# elric20-01A.net
KiCad netlist of a schematic drawn in EAGLE
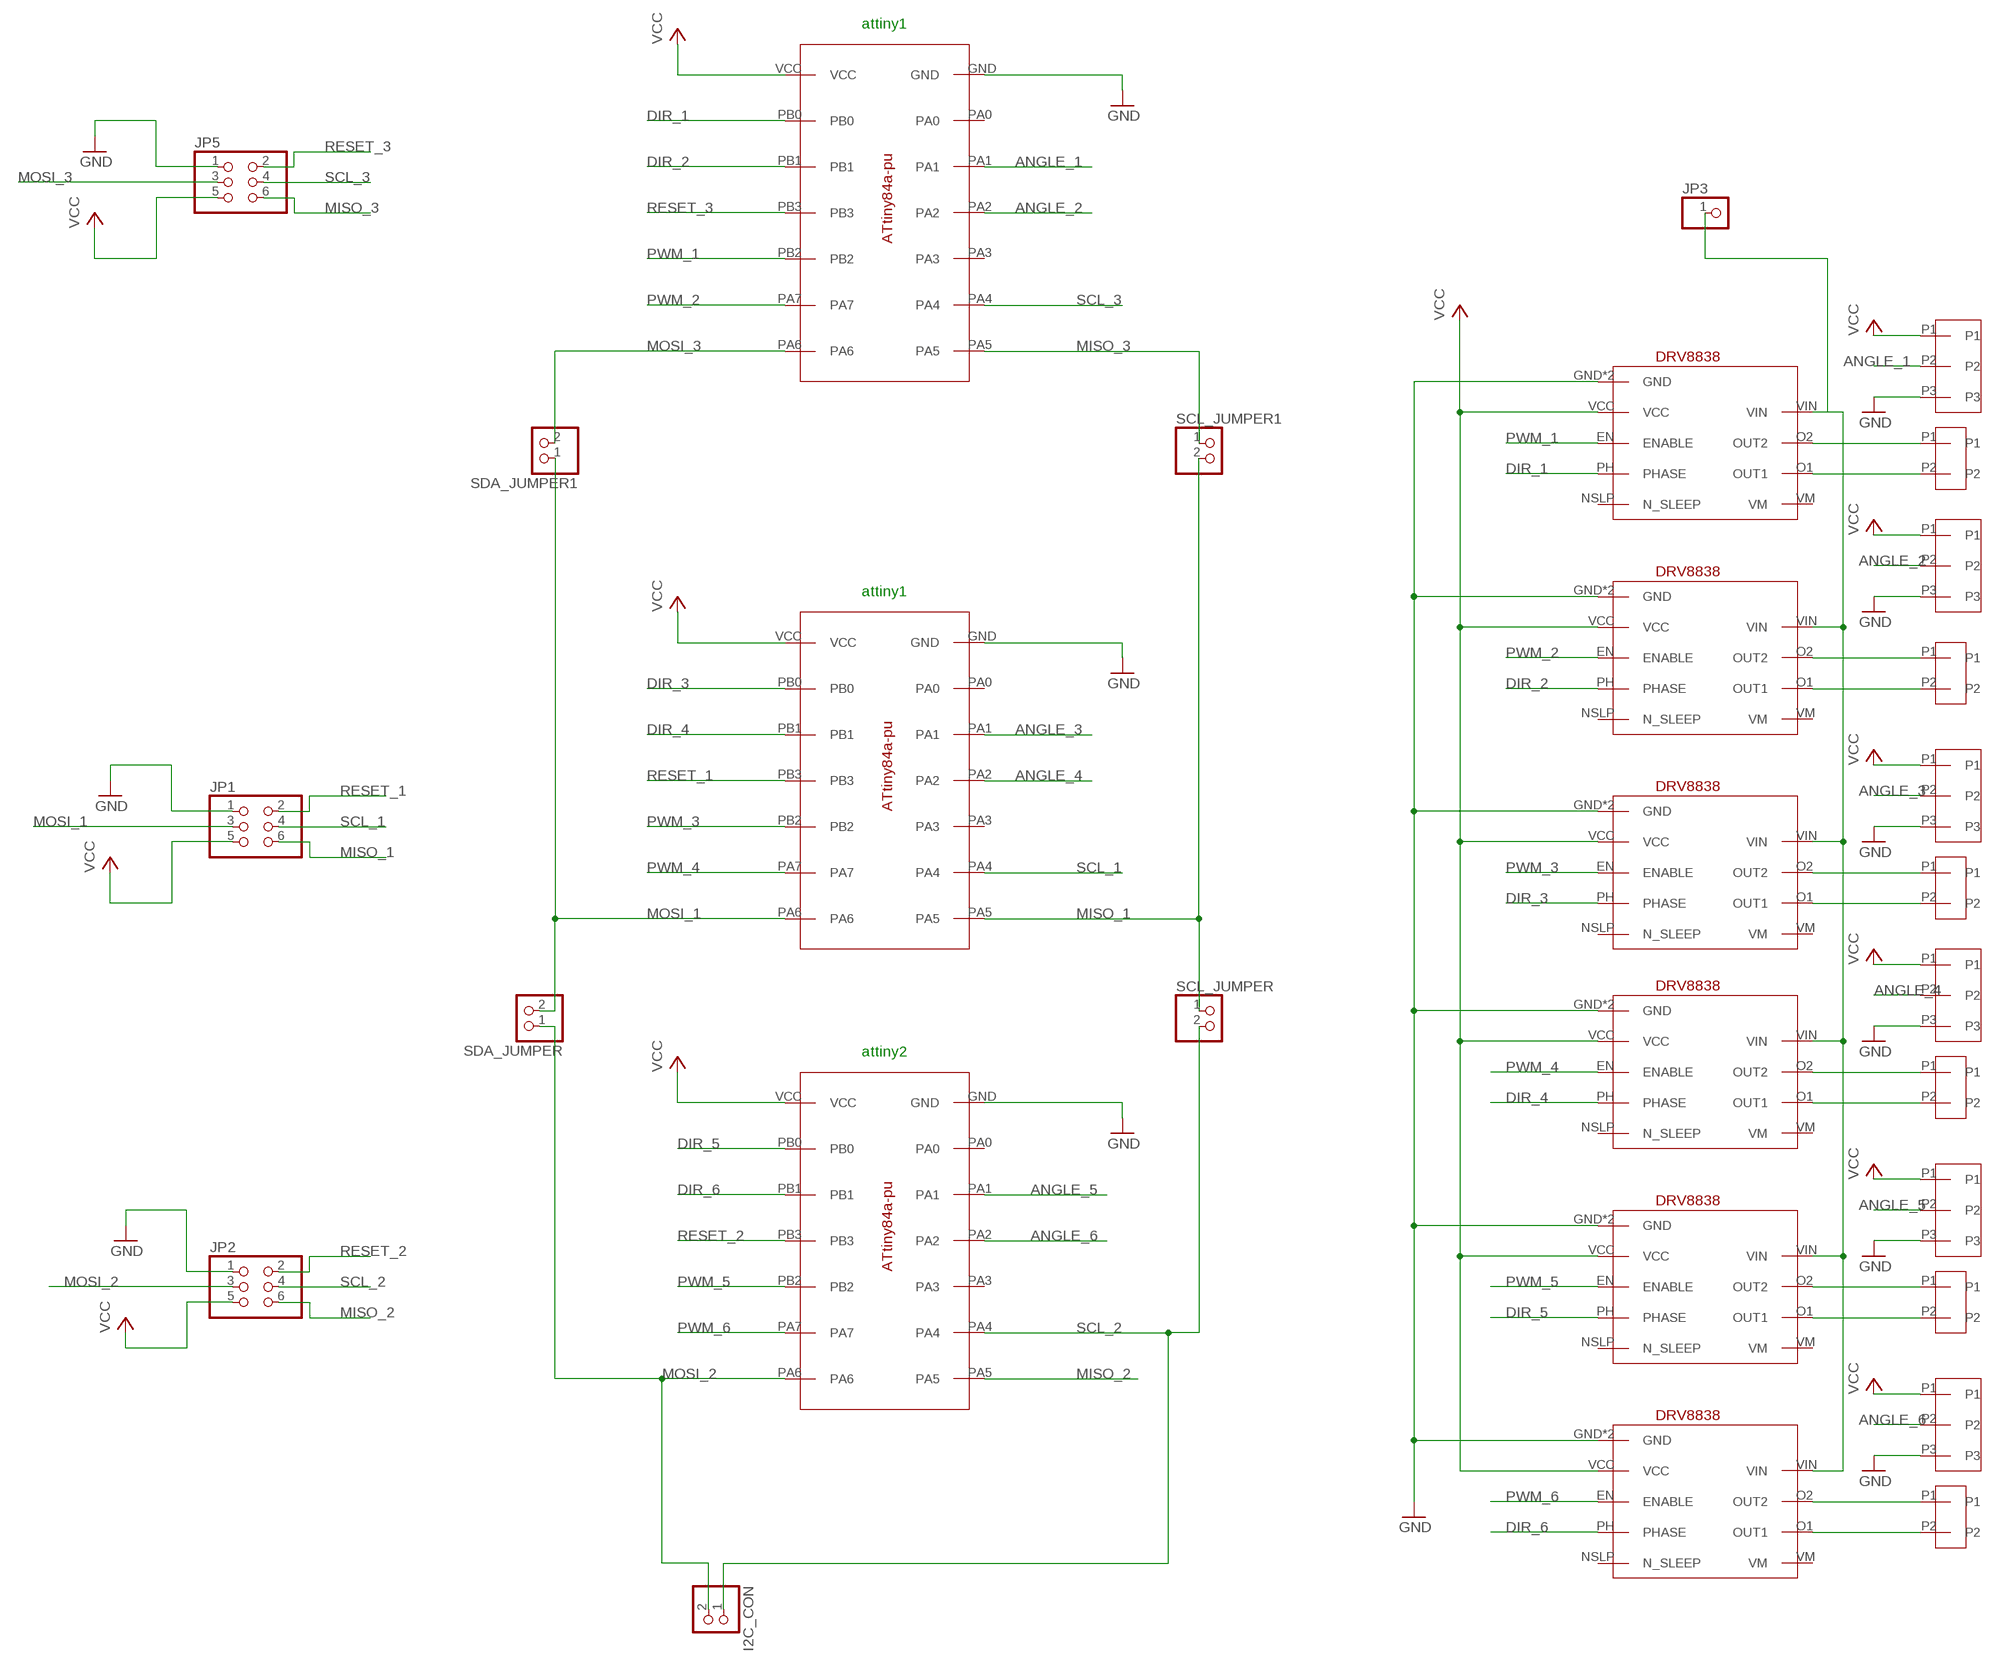
[diagram p0: schematic, sheet 1]

(export (version "E")
  (design (tool "Eeschema 10.0.6"))
  (components
    (comp (ref "I2C_CON")
      (value "PINHD-1X2")
      (footprint "eagle-import:1X02")
      (libsource (lib "eagle-import") (part "PINHD-1X2"))
    )
    (comp (ref "JP1")
      (value "PINHD-2X3")
      (footprint "eagle-import:2X03")
      (libsource (lib "eagle-import") (part "PINHD-2X3"))
    )
    (comp (ref "JP2")
      (value "PINHD-2X3")
      (footprint "eagle-import:2X03")
      (libsource (lib "eagle-import") (part "PINHD-2X3"))
    )
    (comp (ref "JP3")
      (value "PINHD-1X1")
      (footprint "eagle-import:1X01")
      (libsource (lib "eagle-import") (part "PINHD-1X1"))
    )
    (comp (ref "JP5")
      (value "PINHD-2X3")
      (footprint "eagle-import:2X03")
      (libsource (lib "eagle-import") (part "PINHD-2X3"))
    )
    (comp (ref "SCL_JUMPER")
      (value "PINHD-1X2")
      (footprint "eagle-import:1X02")
      (libsource (lib "eagle-import") (part "PINHD-1X2"))
    )
    (comp (ref "SCL_JUMPER1")
      (value "PINHD-1X2")
      (footprint "eagle-import:1X02")
      (libsource (lib "eagle-import") (part "PINHD-1X2"))
    )
    (comp (ref "SDA_JUMPER")
      (value "PINHD-1X2")
      (footprint "eagle-import:1X02")
      (libsource (lib "eagle-import") (part "PINHD-1X2"))
    )
    (comp (ref "SDA_JUMPER1")
      (value "PINHD-1X2")
      (footprint "eagle-import:1X02")
      (libsource (lib "eagle-import") (part "PINHD-1X2"))
    )
    (comp (ref "U$1")
      (value "ATTINY84A-PU")
      (footprint "eagle-import:ATTINY84A-PU")
      (libsource (lib "eagle-import") (part "ATTINY84A-PU"))
    )
    (comp (ref "U$2")
      (value "DRV8838")
      (footprint "eagle-import:DRV8838")
      (libsource (lib "eagle-import") (part "DRV8838"))
    )
    (comp (ref "U$3")
      (value "DRV8838")
      (footprint "eagle-import:DRV8838")
      (libsource (lib "eagle-import") (part "DRV8838"))
    )
    (comp (ref "U$4")
      (value "DRV8838")
      (footprint "eagle-import:DRV8838")
      (libsource (lib "eagle-import") (part "DRV8838"))
    )
    (comp (ref "U$5")
      (value "DRV8838")
      (footprint "eagle-import:DRV8838")
      (libsource (lib "eagle-import") (part "DRV8838"))
    )
    (comp (ref "U$6")
      (value "DRV8838")
      (footprint "eagle-import:DRV8838")
      (libsource (lib "eagle-import") (part "DRV8838"))
    )
    (comp (ref "U$7")
      (value "DRV8838")
      (footprint "eagle-import:DRV8838")
      (libsource (lib "eagle-import") (part "DRV8838"))
    )
    (comp (ref "U$8")
      (value "ATTINY84A-PU")
      (footprint "eagle-import:ATTINY84A-PU")
      (libsource (lib "eagle-import") (part "ATTINY84A-PU"))
    )
    (comp (ref "U$9")
      (value "PAD_SMD_X2_BIG")
      (footprint "eagle-import:PAD_SMD_X2_BIG")
      (libsource (lib "eagle-import") (part "PAD_SMD_X2_BIG"))
    )
    (comp (ref "U$10")
      (value "PAD_SMD_X2_BIG")
      (footprint "eagle-import:PAD_SMD_X2_BIG")
      (libsource (lib "eagle-import") (part "PAD_SMD_X2_BIG"))
    )
    (comp (ref "U$11")
      (value "PAD_SMD_X2_BIG")
      (footprint "eagle-import:PAD_SMD_X2_BIG")
      (libsource (lib "eagle-import") (part "PAD_SMD_X2_BIG"))
    )
    (comp (ref "U$12")
      (value "PAD_SMD_X2_BIG")
      (footprint "eagle-import:PAD_SMD_X2_BIG")
      (libsource (lib "eagle-import") (part "PAD_SMD_X2_BIG"))
    )
    (comp (ref "U$13")
      (value "PAD_SMD_X2_BIG")
      (footprint "eagle-import:PAD_SMD_X2_BIG")
      (libsource (lib "eagle-import") (part "PAD_SMD_X2_BIG"))
    )
    (comp (ref "U$14")
      (value "PAD_SMD_X2_BIG")
      (footprint "eagle-import:PAD_SMD_X2_BIG")
      (libsource (lib "eagle-import") (part "PAD_SMD_X2_BIG"))
    )
    (comp (ref "U$15")
      (value "PAD_SMD_X3")
      (footprint "eagle-import:PAD_SMD_X3")
      (libsource (lib "eagle-import") (part "PAD_SMD_X3"))
    )
    (comp (ref "U$16")
      (value "PAD_SMD_X3")
      (footprint "eagle-import:PAD_SMD_X3")
      (libsource (lib "eagle-import") (part "PAD_SMD_X3"))
    )
    (comp (ref "U$17")
      (value "PAD_SMD_X3")
      (footprint "eagle-import:PAD_SMD_X3")
      (libsource (lib "eagle-import") (part "PAD_SMD_X3"))
    )
    (comp (ref "U$18")
      (value "PAD_SMD_X3")
      (footprint "eagle-import:PAD_SMD_X3")
      (libsource (lib "eagle-import") (part "PAD_SMD_X3"))
    )
    (comp (ref "U$19")
      (value "PAD_SMD_X3")
      (footprint "eagle-import:PAD_SMD_X3")
      (libsource (lib "eagle-import") (part "PAD_SMD_X3"))
    )
    (comp (ref "U$20")
      (value "PAD_SMD_X3")
      (footprint "eagle-import:PAD_SMD_X3")
      (libsource (lib "eagle-import") (part "PAD_SMD_X3"))
    )
    (comp (ref "U$21")
      (value "ATTINY84A-PU")
      (footprint "eagle-import:ATTINY84A-PU")
      (libsource (lib "eagle-import") (part "ATTINY84A-PU"))
    )
  )
  (nets
    (net (code "1") (name "/ANGLE_1") (class "Default")
      (node (ref "U$20") (pin "P2") (pinfunction "P2_P2") (pintype "bidirectional"))
      (node (ref "U$21") (pin "PA1") (pinfunction "PA1_PA1") (pintype "bidirectional"))
    )
    (net (code "2") (name "/ANGLE_2") (class "Default")
      (node (ref "U$19") (pin "P2") (pinfunction "P2_P2") (pintype "bidirectional"))
      (node (ref "U$21") (pin "PA2") (pinfunction "PA2_PA2") (pintype "bidirectional"))
    )
    (net (code "3") (name "/ANGLE_3") (class "Default")
      (node (ref "U$18") (pin "P2") (pinfunction "P2_P2") (pintype "bidirectional"))
      (node (ref "U$8") (pin "PA1") (pinfunction "PA1_PA1") (pintype "bidirectional"))
    )
    (net (code "4") (name "/ANGLE_4") (class "Default")
      (node (ref "U$17") (pin "P2") (pinfunction "P2_P2") (pintype "bidirectional"))
      (node (ref "U$8") (pin "PA2") (pinfunction "PA2_PA2") (pintype "bidirectional"))
    )
    (net (code "5") (name "/ANGLE_5") (class "Default")
      (node (ref "U$1") (pin "PA1") (pinfunction "PA1_PA1") (pintype "bidirectional"))
      (node (ref "U$16") (pin "P2") (pinfunction "P2_P2") (pintype "bidirectional"))
    )
    (net (code "6") (name "/ANGLE_6") (class "Default")
      (node (ref "U$1") (pin "PA2") (pinfunction "PA2_PA2") (pintype "bidirectional"))
      (node (ref "U$15") (pin "P2") (pinfunction "P2_P2") (pintype "bidirectional"))
    )
    (net (code "7") (name "/DIR_1") (class "Default")
      (node (ref "U$2") (pin "PH") (pinfunction "PHASE_PH") (pintype "bidirectional"))
      (node (ref "U$21") (pin "PB0") (pinfunction "PB0_PB0") (pintype "bidirectional"))
    )
    (net (code "8") (name "/DIR_2") (class "Default")
      (node (ref "U$21") (pin "PB1") (pinfunction "PB1_PB1") (pintype "bidirectional"))
      (node (ref "U$3") (pin "PH") (pinfunction "PHASE_PH") (pintype "bidirectional"))
    )
    (net (code "9") (name "/DIR_3") (class "Default")
      (node (ref "U$4") (pin "PH") (pinfunction "PHASE_PH") (pintype "bidirectional"))
      (node (ref "U$8") (pin "PB0") (pinfunction "PB0_PB0") (pintype "bidirectional"))
    )
    (net (code "10") (name "/DIR_4") (class "Default")
      (node (ref "U$5") (pin "PH") (pinfunction "PHASE_PH") (pintype "bidirectional"))
      (node (ref "U$8") (pin "PB1") (pinfunction "PB1_PB1") (pintype "bidirectional"))
    )
    (net (code "11") (name "/DIR_5") (class "Default")
      (node (ref "U$1") (pin "PB0") (pinfunction "PB0_PB0") (pintype "bidirectional"))
      (node (ref "U$6") (pin "PH") (pinfunction "PHASE_PH") (pintype "bidirectional"))
    )
    (net (code "12") (name "/DIR_6") (class "Default")
      (node (ref "U$1") (pin "PB1") (pinfunction "PB1_PB1") (pintype "bidirectional"))
      (node (ref "U$7") (pin "PH") (pinfunction "PHASE_PH") (pintype "bidirectional"))
    )
    (net (code "13") (name "/MISO_1") (class "Default")
      (node (ref "JP1") (pin "6") (pinfunction "6_6") (pintype "passive"))
      (node (ref "SCL_JUMPER") (pin "1") (pinfunction "1_1") (pintype "passive"))
      (node (ref "SCL_JUMPER1") (pin "2") (pinfunction "2_2") (pintype "passive"))
      (node (ref "U$8") (pin "PA5") (pinfunction "PA5_PA5") (pintype "bidirectional"))
    )
    (net (code "14") (name "/MISO_2") (class "Default")
      (node (ref "JP2") (pin "6") (pinfunction "6_6") (pintype "passive"))
      (node (ref "U$1") (pin "PA5") (pinfunction "PA5_PA5") (pintype "bidirectional"))
    )
    (net (code "15") (name "/MISO_3") (class "Default")
      (node (ref "JP5") (pin "6") (pinfunction "6_6") (pintype "passive"))
      (node (ref "SCL_JUMPER1") (pin "1") (pinfunction "1_1") (pintype "passive"))
      (node (ref "U$21") (pin "PA5") (pinfunction "PA5_PA5") (pintype "bidirectional"))
    )
    (net (code "16") (name "/MOSI_1") (class "Default")
      (node (ref "JP1") (pin "3") (pinfunction "3_3") (pintype "passive"))
      (node (ref "SDA_JUMPER") (pin "2") (pinfunction "2_2") (pintype "passive"))
      (node (ref "SDA_JUMPER1") (pin "1") (pinfunction "1_1") (pintype "passive"))
      (node (ref "U$8") (pin "PA6") (pinfunction "PA6_PA6") (pintype "bidirectional"))
    )
    (net (code "17") (name "/MOSI_2") (class "Default")
      (node (ref "I2C_CON") (pin "2") (pinfunction "2_2") (pintype "passive"))
      (node (ref "JP2") (pin "3") (pinfunction "3_3") (pintype "passive"))
      (node (ref "SDA_JUMPER") (pin "1") (pinfunction "1_1") (pintype "passive"))
      (node (ref "U$1") (pin "PA6") (pinfunction "PA6_PA6") (pintype "bidirectional"))
    )
    (net (code "18") (name "/MOSI_3") (class "Default")
      (node (ref "JP5") (pin "3") (pinfunction "3_3") (pintype "passive"))
      (node (ref "SDA_JUMPER1") (pin "2") (pinfunction "2_2") (pintype "passive"))
      (node (ref "U$21") (pin "PA6") (pinfunction "PA6_PA6") (pintype "bidirectional"))
    )
    (net (code "19") (name "/PWM_1") (class "Default")
      (node (ref "U$2") (pin "EN") (pinfunction "ENABLE_EN") (pintype "bidirectional"))
      (node (ref "U$21") (pin "PB2") (pinfunction "PB2_PB2") (pintype "bidirectional"))
    )
    (net (code "20") (name "/PWM_2") (class "Default")
      (node (ref "U$21") (pin "PA7") (pinfunction "PA7_PA7") (pintype "bidirectional"))
      (node (ref "U$3") (pin "EN") (pinfunction "ENABLE_EN") (pintype "bidirectional"))
    )
    (net (code "21") (name "/PWM_3") (class "Default")
      (node (ref "U$4") (pin "EN") (pinfunction "ENABLE_EN") (pintype "bidirectional"))
      (node (ref "U$8") (pin "PB2") (pinfunction "PB2_PB2") (pintype "bidirectional"))
    )
    (net (code "22") (name "/PWM_4") (class "Default")
      (node (ref "U$5") (pin "EN") (pinfunction "ENABLE_EN") (pintype "bidirectional"))
      (node (ref "U$8") (pin "PA7") (pinfunction "PA7_PA7") (pintype "bidirectional"))
    )
    (net (code "23") (name "/PWM_5") (class "Default")
      (node (ref "U$1") (pin "PB2") (pinfunction "PB2_PB2") (pintype "bidirectional"))
      (node (ref "U$6") (pin "EN") (pinfunction "ENABLE_EN") (pintype "bidirectional"))
    )
    (net (code "24") (name "/PWM_6") (class "Default")
      (node (ref "U$1") (pin "PA7") (pinfunction "PA7_PA7") (pintype "bidirectional"))
      (node (ref "U$7") (pin "EN") (pinfunction "ENABLE_EN") (pintype "bidirectional"))
    )
    (net (code "25") (name "/RESET_1") (class "Default")
      (node (ref "JP1") (pin "2") (pinfunction "2_2") (pintype "passive"))
      (node (ref "U$8") (pin "PB3") (pinfunction "PB3_PB3") (pintype "bidirectional"))
    )
    (net (code "26") (name "/RESET_2") (class "Default")
      (node (ref "JP2") (pin "2") (pinfunction "2_2") (pintype "passive"))
      (node (ref "U$1") (pin "PB3") (pinfunction "PB3_PB3") (pintype "bidirectional"))
    )
    (net (code "27") (name "/RESET_3") (class "Default")
      (node (ref "JP5") (pin "2") (pinfunction "2_2") (pintype "passive"))
      (node (ref "U$21") (pin "PB3") (pinfunction "PB3_PB3") (pintype "bidirectional"))
    )
    (net (code "28") (name "/SCL_1") (class "Default")
      (node (ref "JP1") (pin "4") (pinfunction "4_4") (pintype "passive"))
      (node (ref "U$8") (pin "PA4") (pinfunction "PA4_PA4") (pintype "bidirectional"))
    )
    (net (code "29") (name "/SCL_2") (class "Default")
      (node (ref "I2C_CON") (pin "1") (pinfunction "1_1") (pintype "passive"))
      (node (ref "JP2") (pin "4") (pinfunction "4_4") (pintype "passive"))
      (node (ref "SCL_JUMPER") (pin "2") (pinfunction "2_2") (pintype "passive"))
      (node (ref "U$1") (pin "PA4") (pinfunction "PA4_PA4") (pintype "bidirectional"))
    )
    (net (code "30") (name "/SCL_3") (class "Default")
      (node (ref "JP5") (pin "4") (pinfunction "4_4") (pintype "passive"))
      (node (ref "U$21") (pin "PA4") (pinfunction "PA4_PA4") (pintype "bidirectional"))
    )
    (net (code "31") (name "GND") (class "Default")
      (node (ref "JP1") (pin "1") (pinfunction "1_1") (pintype "passive"))
      (node (ref "JP2") (pin "1") (pinfunction "1_1") (pintype "passive"))
      (node (ref "JP5") (pin "1") (pinfunction "1_1") (pintype "passive"))
      (node (ref "U$1") (pin "GND") (pinfunction "GND_GND") (pintype "bidirectional"))
      (node (ref "U$15") (pin "P3") (pinfunction "P3_P3") (pintype "bidirectional"))
      (node (ref "U$16") (pin "P3") (pinfunction "P3_P3") (pintype "bidirectional"))
      (node (ref "U$17") (pin "P3") (pinfunction "P3_P3") (pintype "bidirectional"))
      (node (ref "U$18") (pin "P3") (pinfunction "P3_P3") (pintype "bidirectional"))
      (node (ref "U$19") (pin "P3") (pinfunction "P3_P3") (pintype "bidirectional"))
      (node (ref "U$2") (pin "GND") (pinfunction "GND_GND") (pintype "bidirectional"))
      (node (ref "U$2") (pin "GND2") (pinfunction "GND_GND2") (pintype "bidirectional"))
      (node (ref "U$20") (pin "P3") (pinfunction "P3_P3") (pintype "bidirectional"))
      (node (ref "U$21") (pin "GND") (pinfunction "GND_GND") (pintype "bidirectional"))
      (node (ref "U$3") (pin "GND") (pinfunction "GND_GND") (pintype "bidirectional"))
      (node (ref "U$3") (pin "GND2") (pinfunction "GND_GND2") (pintype "bidirectional"))
      (node (ref "U$4") (pin "GND") (pinfunction "GND_GND") (pintype "bidirectional"))
      (node (ref "U$4") (pin "GND2") (pinfunction "GND_GND2") (pintype "bidirectional"))
      (node (ref "U$5") (pin "GND") (pinfunction "GND_GND") (pintype "bidirectional"))
      (node (ref "U$5") (pin "GND2") (pinfunction "GND_GND2") (pintype "bidirectional"))
      (node (ref "U$6") (pin "GND") (pinfunction "GND_GND") (pintype "bidirectional"))
      (node (ref "U$6") (pin "GND2") (pinfunction "GND_GND2") (pintype "bidirectional"))
      (node (ref "U$7") (pin "GND") (pinfunction "GND_GND") (pintype "bidirectional"))
      (node (ref "U$7") (pin "GND2") (pinfunction "GND_GND2") (pintype "bidirectional"))
      (node (ref "U$8") (pin "GND") (pinfunction "GND_GND") (pintype "bidirectional"))
    )
    (net (code "32") (name "Net-(JP3-Pad1)") (class "Default")
      (node (ref "JP3") (pin "1") (pinfunction "1_1") (pintype "passive"))
      (node (ref "U$2") (pin "VIN") (pinfunction "VIN_VIN") (pintype "bidirectional"))
      (node (ref "U$3") (pin "VIN") (pinfunction "VIN_VIN") (pintype "bidirectional"))
      (node (ref "U$4") (pin "VIN") (pinfunction "VIN_VIN") (pintype "bidirectional"))
      (node (ref "U$5") (pin "VIN") (pinfunction "VIN_VIN") (pintype "bidirectional"))
      (node (ref "U$6") (pin "VIN") (pinfunction "VIN_VIN") (pintype "bidirectional"))
      (node (ref "U$7") (pin "VIN") (pinfunction "VIN_VIN") (pintype "bidirectional"))
    )
    (net (code "33") (name "Net-(U$2-OUT1)") (class "Default")
      (node (ref "U$2") (pin "O1") (pinfunction "OUT1_O1") (pintype "bidirectional"))
      (node (ref "U$9") (pin "P2") (pinfunction "P2_P2") (pintype "bidirectional"))
    )
    (net (code "34") (name "Net-(U$2-OUT2)") (class "Default")
      (node (ref "U$2") (pin "O2") (pinfunction "OUT2_O2") (pintype "bidirectional"))
      (node (ref "U$9") (pin "P1") (pinfunction "P1_P1") (pintype "bidirectional"))
    )
    (net (code "35") (name "Net-(U$3-OUT1)") (class "Default")
      (node (ref "U$10") (pin "P2") (pinfunction "P2_P2") (pintype "bidirectional"))
      (node (ref "U$3") (pin "O1") (pinfunction "OUT1_O1") (pintype "bidirectional"))
    )
    (net (code "36") (name "Net-(U$3-OUT2)") (class "Default")
      (node (ref "U$10") (pin "P1") (pinfunction "P1_P1") (pintype "bidirectional"))
      (node (ref "U$3") (pin "O2") (pinfunction "OUT2_O2") (pintype "bidirectional"))
    )
    (net (code "37") (name "Net-(U$4-OUT1)") (class "Default")
      (node (ref "U$11") (pin "P2") (pinfunction "P2_P2") (pintype "bidirectional"))
      (node (ref "U$4") (pin "O1") (pinfunction "OUT1_O1") (pintype "bidirectional"))
    )
    (net (code "38") (name "Net-(U$4-OUT2)") (class "Default")
      (node (ref "U$11") (pin "P1") (pinfunction "P1_P1") (pintype "bidirectional"))
      (node (ref "U$4") (pin "O2") (pinfunction "OUT2_O2") (pintype "bidirectional"))
    )
    (net (code "39") (name "Net-(U$5-OUT1)") (class "Default")
      (node (ref "U$12") (pin "P2") (pinfunction "P2_P2") (pintype "bidirectional"))
      (node (ref "U$5") (pin "O1") (pinfunction "OUT1_O1") (pintype "bidirectional"))
    )
    (net (code "40") (name "Net-(U$5-OUT2)") (class "Default")
      (node (ref "U$12") (pin "P1") (pinfunction "P1_P1") (pintype "bidirectional"))
      (node (ref "U$5") (pin "O2") (pinfunction "OUT2_O2") (pintype "bidirectional"))
    )
    (net (code "41") (name "Net-(U$6-OUT1)") (class "Default")
      (node (ref "U$13") (pin "P2") (pinfunction "P2_P2") (pintype "bidirectional"))
      (node (ref "U$6") (pin "O1") (pinfunction "OUT1_O1") (pintype "bidirectional"))
    )
    (net (code "42") (name "Net-(U$6-OUT2)") (class "Default")
      (node (ref "U$13") (pin "P1") (pinfunction "P1_P1") (pintype "bidirectional"))
      (node (ref "U$6") (pin "O2") (pinfunction "OUT2_O2") (pintype "bidirectional"))
    )
    (net (code "43") (name "Net-(U$7-OUT1)") (class "Default")
      (node (ref "U$14") (pin "P2") (pinfunction "P2_P2") (pintype "bidirectional"))
      (node (ref "U$7") (pin "O1") (pinfunction "OUT1_O1") (pintype "bidirectional"))
    )
    (net (code "44") (name "Net-(U$7-OUT2)") (class "Default")
      (node (ref "U$14") (pin "P1") (pinfunction "P1_P1") (pintype "bidirectional"))
      (node (ref "U$7") (pin "O2") (pinfunction "OUT2_O2") (pintype "bidirectional"))
    )
    (net (code "45") (name "VCC") (class "Default")
      (node (ref "JP1") (pin "5") (pinfunction "5_5") (pintype "passive"))
      (node (ref "JP2") (pin "5") (pinfunction "5_5") (pintype "passive"))
      (node (ref "JP5") (pin "5") (pinfunction "5_5") (pintype "passive"))
      (node (ref "U$1") (pin "VCC") (pinfunction "VCC_VCC") (pintype "bidirectional"))
      (node (ref "U$15") (pin "P1") (pinfunction "P1_P1") (pintype "bidirectional"))
      (node (ref "U$16") (pin "P1") (pinfunction "P1_P1") (pintype "bidirectional"))
      (node (ref "U$17") (pin "P1") (pinfunction "P1_P1") (pintype "bidirectional"))
      (node (ref "U$18") (pin "P1") (pinfunction "P1_P1") (pintype "bidirectional"))
      (node (ref "U$19") (pin "P1") (pinfunction "P1_P1") (pintype "bidirectional"))
      (node (ref "U$2") (pin "VCC") (pinfunction "VCC_VCC") (pintype "bidirectional"))
      (node (ref "U$20") (pin "P1") (pinfunction "P1_P1") (pintype "bidirectional"))
      (node (ref "U$21") (pin "VCC") (pinfunction "VCC_VCC") (pintype "bidirectional"))
      (node (ref "U$3") (pin "VCC") (pinfunction "VCC_VCC") (pintype "bidirectional"))
      (node (ref "U$4") (pin "VCC") (pinfunction "VCC_VCC") (pintype "bidirectional"))
      (node (ref "U$5") (pin "VCC") (pinfunction "VCC_VCC") (pintype "bidirectional"))
      (node (ref "U$6") (pin "VCC") (pinfunction "VCC_VCC") (pintype "bidirectional"))
      (node (ref "U$7") (pin "VCC") (pinfunction "VCC_VCC") (pintype "bidirectional"))
      (node (ref "U$8") (pin "VCC") (pinfunction "VCC_VCC") (pintype "bidirectional"))
    )
    (net (code "46") (name "unconnected-(U$1-PadPA0)") (class "Default")
      (node (ref "U$1") (pin "PA0") (pinfunction "PA0_PA0") (pintype "bidirectional"))
    )
    (net (code "47") (name "unconnected-(U$1-PadPA3)") (class "Default")
      (node (ref "U$1") (pin "PA3") (pinfunction "PA3_PA3") (pintype "bidirectional"))
    )
    (net (code "48") (name "unconnected-(U$2-N_SLEEP-PadNSLP)") (class "Default")
      (node (ref "U$2") (pin "NSLP") (pinfunction "N_SLEEP_NSLP") (pintype "bidirectional"))
    )
    (net (code "49") (name "unconnected-(U$2-PadVM)") (class "Default")
      (node (ref "U$2") (pin "VM") (pinfunction "VM_VM") (pintype "bidirectional"))
    )
    (net (code "50") (name "unconnected-(U$3-N_SLEEP-PadNSLP)") (class "Default")
      (node (ref "U$3") (pin "NSLP") (pinfunction "N_SLEEP_NSLP") (pintype "bidirectional"))
    )
    (net (code "51") (name "unconnected-(U$3-PadVM)") (class "Default")
      (node (ref "U$3") (pin "VM") (pinfunction "VM_VM") (pintype "bidirectional"))
    )
    (net (code "52") (name "unconnected-(U$4-N_SLEEP-PadNSLP)") (class "Default")
      (node (ref "U$4") (pin "NSLP") (pinfunction "N_SLEEP_NSLP") (pintype "bidirectional"))
    )
    (net (code "53") (name "unconnected-(U$4-PadVM)") (class "Default")
      (node (ref "U$4") (pin "VM") (pinfunction "VM_VM") (pintype "bidirectional"))
    )
    (net (code "54") (name "unconnected-(U$5-N_SLEEP-PadNSLP)") (class "Default")
      (node (ref "U$5") (pin "NSLP") (pinfunction "N_SLEEP_NSLP") (pintype "bidirectional"))
    )
    (net (code "55") (name "unconnected-(U$5-PadVM)") (class "Default")
      (node (ref "U$5") (pin "VM") (pinfunction "VM_VM") (pintype "bidirectional"))
    )
    (net (code "56") (name "unconnected-(U$6-N_SLEEP-PadNSLP)") (class "Default")
      (node (ref "U$6") (pin "NSLP") (pinfunction "N_SLEEP_NSLP") (pintype "bidirectional"))
    )
    (net (code "57") (name "unconnected-(U$6-PadVM)") (class "Default")
      (node (ref "U$6") (pin "VM") (pinfunction "VM_VM") (pintype "bidirectional"))
    )
    (net (code "58") (name "unconnected-(U$7-N_SLEEP-PadNSLP)") (class "Default")
      (node (ref "U$7") (pin "NSLP") (pinfunction "N_SLEEP_NSLP") (pintype "bidirectional"))
    )
    (net (code "59") (name "unconnected-(U$7-PadVM)") (class "Default")
      (node (ref "U$7") (pin "VM") (pinfunction "VM_VM") (pintype "bidirectional"))
    )
    (net (code "60") (name "unconnected-(U$8-PadPA0)") (class "Default")
      (node (ref "U$8") (pin "PA0") (pinfunction "PA0_PA0") (pintype "bidirectional"))
    )
    (net (code "61") (name "unconnected-(U$8-PadPA3)") (class "Default")
      (node (ref "U$8") (pin "PA3") (pinfunction "PA3_PA3") (pintype "bidirectional"))
    )
    (net (code "62") (name "unconnected-(U$21-PadPA0)") (class "Default")
      (node (ref "U$21") (pin "PA0") (pinfunction "PA0_PA0") (pintype "bidirectional"))
    )
    (net (code "63") (name "unconnected-(U$21-PadPA3)") (class "Default")
      (node (ref "U$21") (pin "PA3") (pinfunction "PA3_PA3") (pintype "bidirectional"))
    )
  )
)
